# switch_termi.net
KiCad netlist of a schematic drawn in EAGLE
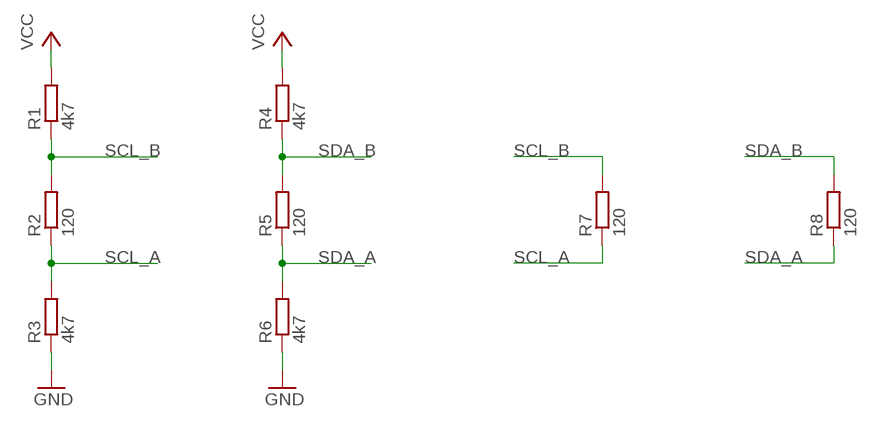
[diagram p0: schematic, sheet 1]

(export (version "E")
  (design (tool "Eeschema 10.0.6"))
  (components
    (comp (ref "R1")
      (value "4k7")
      (footprint "eagle-import:R1206")
      (libsource (lib "eagle-import") (part "R-EU_R1206"))
    )
    (comp (ref "R2")
      (value "120")
      (footprint "eagle-import:R1206")
      (libsource (lib "eagle-import") (part "R-EU_R1206"))
    )
    (comp (ref "R3")
      (value "4k7")
      (footprint "eagle-import:R1206")
      (libsource (lib "eagle-import") (part "R-EU_R1206"))
    )
    (comp (ref "R4")
      (value "4k7")
      (footprint "eagle-import:R1206")
      (libsource (lib "eagle-import") (part "R-EU_R1206"))
    )
    (comp (ref "R5")
      (value "120")
      (footprint "eagle-import:R1206")
      (libsource (lib "eagle-import") (part "R-EU_R1206"))
    )
    (comp (ref "R6")
      (value "4k7")
      (footprint "eagle-import:R1206")
      (libsource (lib "eagle-import") (part "R-EU_R1206"))
    )
    (comp (ref "R7")
      (value "120")
      (footprint "eagle-import:R1206")
      (libsource (lib "eagle-import") (part "R-EU_R1206"))
    )
    (comp (ref "R8")
      (value "120")
      (footprint "eagle-import:R1206")
      (libsource (lib "eagle-import") (part "R-EU_R1206"))
    )
  )
  (nets
    (net (code "1") (name "/SCL_A") (class "Default")
      (node (ref "R2") (pin "1") (pinfunction "1_1") (pintype "passive"))
      (node (ref "R3") (pin "2") (pinfunction "2_2") (pintype "passive"))
      (node (ref "R7") (pin "1") (pinfunction "1_1") (pintype "passive"))
    )
    (net (code "2") (name "/SCL_B") (class "Default")
      (node (ref "R1") (pin "1") (pinfunction "1_1") (pintype "passive"))
      (node (ref "R2") (pin "2") (pinfunction "2_2") (pintype "passive"))
      (node (ref "R7") (pin "2") (pinfunction "2_2") (pintype "passive"))
    )
    (net (code "3") (name "/SDA_A") (class "Default")
      (node (ref "R5") (pin "1") (pinfunction "1_1") (pintype "passive"))
      (node (ref "R6") (pin "2") (pinfunction "2_2") (pintype "passive"))
      (node (ref "R8") (pin "1") (pinfunction "1_1") (pintype "passive"))
    )
    (net (code "4") (name "/SDA_B") (class "Default")
      (node (ref "R4") (pin "1") (pinfunction "1_1") (pintype "passive"))
      (node (ref "R5") (pin "2") (pinfunction "2_2") (pintype "passive"))
      (node (ref "R8") (pin "2") (pinfunction "2_2") (pintype "passive"))
    )
    (net (code "5") (name "GND") (class "Default")
      (node (ref "R3") (pin "1") (pinfunction "1_1") (pintype "passive"))
      (node (ref "R6") (pin "1") (pinfunction "1_1") (pintype "passive"))
    )
    (net (code "6") (name "VCC") (class "Default")
      (node (ref "R1") (pin "2") (pinfunction "2_2") (pintype "passive"))
      (node (ref "R4") (pin "2") (pinfunction "2_2") (pintype "passive"))
    )
  )
)
